# IO_FMU_REV_1A.net
KiCad netlist of a schematic drawn in Altium Designer
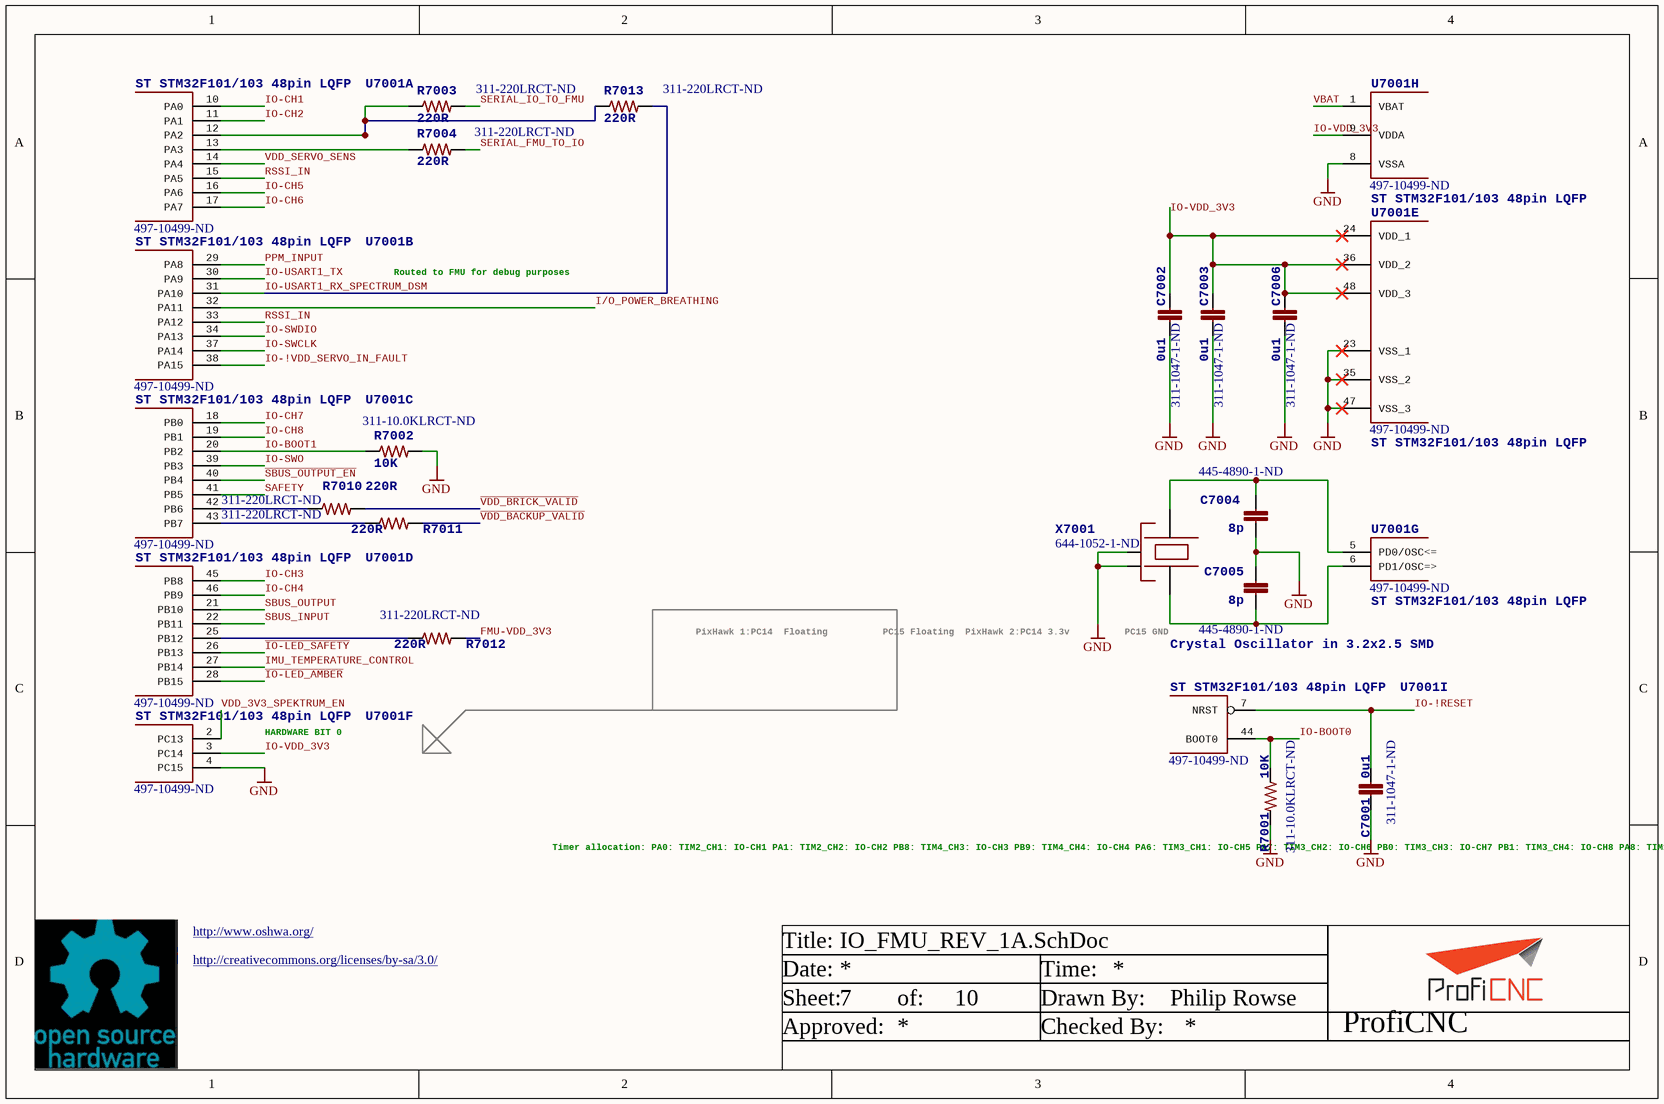
[diagram p0: IO_FMU_REV_1A.SchDoc]

(export (version "E")
  (design (tool "Eeschema 10.0.6"))
  (components
    (comp (ref "C7001")
      (value "0u1")
      (footprint "0402-CAP")
      (description "CAP CER 0.1UF 16V Y5V 0402")
      (fields
        (field (name "PARTNO") "CC0402ZRY5V7BB104")
        (field (name "SUPPLIER PART NUMBER 1") "311-1047-1-ND")
        (field (name "3DR_PARTNO") "ECM0700")
      )
      (libsource (lib "") (part "CAP0402_1"))
    )
    (comp (ref "C7002")
      (value "0u1")
      (footprint "0402-CAP")
      (description "CAP CER 0.1UF 16V Y5V 0402")
      (fields
        (field (name "PARTNO") "CC0402ZRY5V7BB104")
        (field (name "SUPPLIER PART NUMBER 1") "311-1047-1-ND")
        (field (name "3DR_PARTNO") "ECM0700")
      )
      (libsource (lib "pixhawk2") (part "CAP0402"))
    )
    (comp (ref "C7003")
      (value "0u1")
      (footprint "0402-CAP")
      (description "CAP CER 0.1UF 16V Y5V 0402")
      (fields
        (field (name "PARTNO") "CC0402ZRY5V7BB104")
        (field (name "SUPPLIER PART NUMBER 1") "311-1047-1-ND")
        (field (name "3DR_PARTNO") "ECM0700")
      )
      (libsource (lib "pixhawk2") (part "CAP0402"))
    )
    (comp (ref "C7004")
      (value "8p")
      (footprint "0402-CAP")
      (description "CAP CER 8PF 50V C0G 0402")
      (fields
        (field (name "PARTNO") "C1005C0G1H080C")
        (field (name "SUPPLIER PART NUMBER 1") "445-4890-1-ND")
        (field (name "3DR_PARTNO") "ECM0710")
      )
      (libsource (lib "pixhawk2") (part "CAP0402"))
    )
    (comp (ref "C7005")
      (value "8p")
      (footprint "0402-CAP")
      (description "CAP CER 8PF 50V C0G 0402")
      (fields
        (field (name "PARTNO") "C1005C0G1H080C")
        (field (name "SUPPLIER PART NUMBER 1") "445-4890-1-ND")
        (field (name "3DR_PARTNO") "ECM0710")
      )
      (libsource (lib "pixhawk2") (part "CAP0402"))
    )
    (comp (ref "C7006")
      (value "0u1")
      (footprint "0402-CAP")
      (description "CAP CER 0.1UF 16V Y5V 0402")
      (fields
        (field (name "PARTNO") "CC0402ZRY5V7BB104")
        (field (name "SUPPLIER PART NUMBER 1") "311-1047-1-ND")
        (field (name "3DR_PARTNO") "ECM0700")
      )
      (libsource (lib "pixhawk2") (part "CAP0402"))
    )
    (comp (ref "R7001")
      (value "10K")
      (footprint "0402-RES")
      (description "RES 10K OHM 1/16W 1% 0402 SMD")
      (fields
        (field (name "PARTNO") "RC0402FR-0710KL")
        (field (name "SUPPLIER PART NUMBER 1") "311-10.0KLRCT-ND")
        (field (name "3DR_PARTNO") "ECM0800")
      )
      (libsource (lib "pixhawk2") (part "RESISTOR0402-RES"))
    )
    (comp (ref "R7002")
      (value "10K")
      (footprint "0402-RES")
      (description "RES 10K OHM 1/16W 1% 0402 SMD")
      (fields
        (field (name "PARTNO") "RC0402FR-0710KL")
        (field (name "SUPPLIER PART NUMBER 1") "311-10.0KLRCT-ND")
        (field (name "3DR_PARTNO") "ECM0800")
      )
      (libsource (lib "pixhawk2") (part "RESISTOR0402-RES"))
    )
    (comp (ref "R7003")
      (value "220R")
      (footprint "0402-RES")
      (description "RES 220 OHM 1/16W 1% 0402 SMD")
      (fields
        (field (name "PARTNO") "RC0402FR-07220RL")
        (field (name "SUPPLIER PART NUMBER 1") "311-220LRCT-ND")
        (field (name "3DR_PARTNO") "ECM0821")
      )
      (libsource (lib "pixhawk2") (part "RESISTOR0402-RES"))
    )
    (comp (ref "R7004")
      (value "220R")
      (footprint "0402-RES")
      (description "RES 220 OHM 1/16W 1% 0402 SMD")
      (fields
        (field (name "PARTNO") "RC0402FR-07220RL")
        (field (name "SUPPLIER PART NUMBER 1") "311-220LRCT-ND")
        (field (name "3DR_PARTNO") "ECM0821")
      )
      (libsource (lib "pixhawk2") (part "RESISTOR0402-RES"))
    )
    (comp (ref "R7010")
      (value "220R")
      (footprint "0402-RES")
      (description "RES 220 OHM 1/16W 1% 0402 SMD")
      (fields
        (field (name "PARTNO") "RC0402FR-07220RL")
        (field (name "SUPPLIER PART NUMBER 1") "311-220LRCT-ND")
        (field (name "3DR_PARTNO") "ECM0821")
      )
      (libsource (lib "pixhawk2") (part "RESISTOR0402-RES"))
    )
    (comp (ref "R7011")
      (value "220R")
      (footprint "0402-RES")
      (description "RES 220 OHM 1/16W 1% 0402 SMD")
      (fields
        (field (name "PARTNO") "RC0402FR-07220RL")
        (field (name "SUPPLIER PART NUMBER 1") "311-220LRCT-ND")
        (field (name "3DR_PARTNO") "ECM0821")
      )
      (libsource (lib "pixhawk2") (part "RESISTOR0402-RES"))
    )
    (comp (ref "R7012")
      (value "220R")
      (footprint "0402-RES")
      (description "RES 220 OHM 1/16W 1% 0402 SMD")
      (fields
        (field (name "PARTNO") "RC0402FR-07220RL")
        (field (name "SUPPLIER PART NUMBER 1") "311-220LRCT-ND")
        (field (name "3DR_PARTNO") "ECM0821")
      )
      (libsource (lib "pixhawk2") (part "RESISTOR0402-RES"))
    )
    (comp (ref "R7013")
      (value "220R")
      (footprint "0402-RES")
      (description "RES 220 OHM 1/16W 1% 0402 SMD")
      (fields
        (field (name "PARTNO") "RC0402FR-07220RL")
        (field (name "SUPPLIER PART NUMBER 1") "311-220LRCT-ND")
        (field (name "3DR_PARTNO") "ECM0821")
      )
      (libsource (lib "pixhawk2") (part "RESISTOR0402-RES"))
    )
    (comp (ref "U7001")
      (value "ST STM32F101/103 48pin LQFP")
      (footprint "TQFP48")
      (description "MCU 32BIT ARM 64K FLASH 48LQFP")
      (fields (field (name "SUPPLIER PART NUMBER 1") "497-10499-ND") (field (name "3DR_PARTNO") "EMC0842"))
      (libsource (lib "pixhawk2") (part "STM32F10XCXT6"))
    )
    (comp (ref "X7001")
      (value "Crystal Oscillator in 3.2x2.5 SMD")
      (footprint "OSCILLATOR-3.2X2.5")
      (description "CRYSTAL 24MHZ 8PF SMD")
      (fields
        (field (name "SUPPLIER PART NUMBER 1") "644-1052-1-ND")
        (field (name "3DR_PARTNO") "ECM0708")
        (field (name "PARTNO") "NX3225SA-24.000MHZ-STD-CSR-1")
      )
      (libsource (lib "pixhawk2") (part "OSCILLATOR-3.2X2.5"))
    )
  )
  (nets
    (net (code "1") (name "/FMU-VDD_3V3") (class "Default")
      (node (ref "R7012") (pin "P$2") (pinfunction "2_P$2") (pintype "passive"))
    )
    (net (code "2") (name "/IMU_TEMPERATURE_CONTROL") (class "Default")
      (node (ref "U7001") (pin "27") (pinfunction "PB14_27") (pintype "passive"))
    )
    (net (code "3") (name "/IO-!RESET") (class "Default")
      (node (ref "C7001") (pin "P$2") (pinfunction "2_P$2") (pintype "passive"))
      (node (ref "U7001") (pin "7") (pinfunction "NRST_7") (pintype "passive"))
    )
    (net (code "4") (name "/IO-!VDD_SERVO_IN_FAULT") (class "Default")
      (node (ref "U7001") (pin "38") (pinfunction "PA15_38") (pintype "passive"))
    )
    (net (code "5") (name "/IO-BOOT0") (class "Default")
      (node (ref "R7001") (pin "P$1") (pinfunction "1_P$1") (pintype "passive"))
      (node (ref "U7001") (pin "44") (pinfunction "BOOT0_44") (pintype "passive"))
    )
    (net (code "6") (name "/IO-BOOT1") (class "Default")
      (node (ref "R7002") (pin "P$1") (pinfunction "1_P$1") (pintype "passive"))
      (node (ref "U7001") (pin "20") (pinfunction "PB2_20") (pintype "passive"))
    )
    (net (code "7") (name "/IO-CH1") (class "Default")
      (node (ref "U7001") (pin "10") (pinfunction "PA0_10") (pintype "passive"))
    )
    (net (code "8") (name "/IO-CH2") (class "Default")
      (node (ref "U7001") (pin "11") (pinfunction "PA1_11") (pintype "passive"))
    )
    (net (code "9") (name "/IO-CH3") (class "Default")
      (node (ref "U7001") (pin "45") (pinfunction "PB8_45") (pintype "passive"))
    )
    (net (code "10") (name "/IO-CH4") (class "Default")
      (node (ref "U7001") (pin "46") (pinfunction "PB9_46") (pintype "passive"))
    )
    (net (code "11") (name "/IO-CH5") (class "Default")
      (node (ref "U7001") (pin "16") (pinfunction "PA6_16") (pintype "passive"))
    )
    (net (code "12") (name "/IO-CH6") (class "Default")
      (node (ref "U7001") (pin "17") (pinfunction "PA7_17") (pintype "passive"))
    )
    (net (code "13") (name "/IO-CH7") (class "Default")
      (node (ref "U7001") (pin "18") (pinfunction "PB0_18") (pintype "passive"))
    )
    (net (code "14") (name "/IO-CH8") (class "Default")
      (node (ref "U7001") (pin "19") (pinfunction "PB1_19") (pintype "passive"))
    )
    (net (code "15") (name "/IO-SWCLK") (class "Default")
      (node (ref "U7001") (pin "37") (pinfunction "PA14_37") (pintype "passive"))
    )
    (net (code "16") (name "/IO-SWDIO") (class "Default")
      (node (ref "U7001") (pin "34") (pinfunction "PA13_34") (pintype "passive"))
    )
    (net (code "17") (name "/IO-SWO") (class "Default")
      (node (ref "U7001") (pin "39") (pinfunction "PB3_39") (pintype "passive"))
    )
    (net (code "18") (name "/IO-USART1_RX_SPECTRUM_DSM") (class "Default")
      (node (ref "R7013") (pin "P$2") (pinfunction "2_P$2") (pintype "passive"))
      (node (ref "U7001") (pin "31") (pinfunction "PA10_31") (pintype "passive"))
    )
    (net (code "19") (name "/IO-USART1_TX") (class "Default")
      (node (ref "U7001") (pin "30") (pinfunction "PA9_30") (pintype "passive"))
    )
    (net (code "20") (name "/IO-VDD_3V3") (class "Default")
      (node (ref "C7002") (pin "P$1") (pinfunction "1_P$1") (pintype "passive"))
      (node (ref "C7003") (pin "P$1") (pinfunction "1_P$1") (pintype "passive"))
      (node (ref "C7006") (pin "P$1") (pinfunction "1_P$1") (pintype "passive"))
      (node (ref "U7001") (pin "24") (pinfunction "VDD_1_24") (pintype "power_in"))
      (node (ref "U7001") (pin "3") (pinfunction "PC14_3") (pintype "passive"))
      (node (ref "U7001") (pin "36") (pinfunction "VDD_2_36") (pintype "power_in"))
      (node (ref "U7001") (pin "48") (pinfunction "VDD_3_48") (pintype "power_in"))
      (node (ref "U7001") (pin "9") (pinfunction "VDDA_9") (pintype "power_in"))
    )
    (net (code "21") (name "/I{slash}O_POWER_BREATHING") (class "Default")
      (node (ref "U7001") (pin "32") (pinfunction "PA11_32") (pintype "passive"))
    )
    (net (code "22") (name "/PPM_INPUT") (class "Default")
      (node (ref "U7001") (pin "29") (pinfunction "PA8_29") (pintype "passive"))
    )
    (net (code "23") (name "/RSSI_IN") (class "Default")
      (node (ref "U7001") (pin "15") (pinfunction "PA5_15") (pintype "passive"))
      (node (ref "U7001") (pin "33") (pinfunction "PA12_33") (pintype "passive"))
    )
    (net (code "24") (name "/SAFETY") (class "Default")
      (node (ref "U7001") (pin "41") (pinfunction "PB5_41") (pintype "passive"))
    )
    (net (code "25") (name "/SBUS_INPUT") (class "Default")
      (node (ref "U7001") (pin "22") (pinfunction "PB11_22") (pintype "passive"))
    )
    (net (code "26") (name "/SBUS_OUTPUT") (class "Default")
      (node (ref "U7001") (pin "21") (pinfunction "PB10_21") (pintype "passive"))
    )
    (net (code "27") (name "/SERIAL_FMU_TO_IO") (class "Default")
      (node (ref "R7004") (pin "P$2") (pinfunction "2_P$2") (pintype "passive"))
    )
    (net (code "28") (name "/SERIAL_IO_TO_FMU") (class "Default")
      (node (ref "R7003") (pin "P$2") (pinfunction "2_P$2") (pintype "passive"))
    )
    (net (code "29") (name "/VBAT") (class "Default")
      (node (ref "U7001") (pin "1") (pinfunction "VBAT_1") (pintype "power_in"))
    )
    (net (code "30") (name "/VDD_3V3_SPEKTRUM_EN") (class "Default")
      (node (ref "U7001") (pin "2") (pinfunction "PC13_2") (pintype "passive"))
    )
    (net (code "31") (name "/VDD_SERVO_SENS") (class "Default")
      (node (ref "U7001") (pin "14") (pinfunction "PA4_14") (pintype "passive"))
    )
    (net (code "32") (name "/~{IO-LED_AMBER}") (class "Default")
      (node (ref "U7001") (pin "28") (pinfunction "PB15_28") (pintype "passive"))
    )
    (net (code "33") (name "/~{IO-LED_SAFETY}") (class "Default")
      (node (ref "U7001") (pin "26") (pinfunction "PB13_26") (pintype "passive"))
    )
    (net (code "34") (name "/~{SBUS_OUTPUT_EN}") (class "Default")
      (node (ref "U7001") (pin "40") (pinfunction "PB4_40") (pintype "passive"))
    )
    (net (code "35") (name "/~{VDD_BACKUP_VALID}") (class "Default")
      (node (ref "R7011") (pin "P$2") (pinfunction "2_P$2") (pintype "passive"))
    )
    (net (code "36") (name "/~{VDD_BRICK_VALID}") (class "Default")
      (node (ref "R7010") (pin "P$2") (pinfunction "2_P$2") (pintype "passive"))
    )
    (net (code "37") (name "GND") (class "Default")
      (node (ref "C7001") (pin "P$1") (pinfunction "1_P$1") (pintype "passive"))
      (node (ref "C7002") (pin "P$2") (pinfunction "2_P$2") (pintype "passive"))
      (node (ref "C7003") (pin "P$2") (pinfunction "2_P$2") (pintype "passive"))
      (node (ref "C7004") (pin "P$2") (pinfunction "2_P$2") (pintype "passive"))
      (node (ref "C7005") (pin "P$1") (pinfunction "1_P$1") (pintype "passive"))
      (node (ref "C7006") (pin "P$2") (pinfunction "2_P$2") (pintype "passive"))
      (node (ref "R7001") (pin "P$2") (pinfunction "2_P$2") (pintype "passive"))
      (node (ref "R7002") (pin "P$2") (pinfunction "2_P$2") (pintype "passive"))
      (node (ref "U7001") (pin "23") (pinfunction "VSS_1_23") (pintype "power_in"))
      (node (ref "U7001") (pin "35") (pinfunction "VSS_2_35") (pintype "power_in"))
      (node (ref "U7001") (pin "4") (pinfunction "PC15_4") (pintype "passive"))
      (node (ref "U7001") (pin "47") (pinfunction "VSS_3_47") (pintype "power_in"))
      (node (ref "U7001") (pin "8") (pinfunction "VSSA_8") (pintype "power_in"))
      (node (ref "X7001") (pin "2") (pinfunction "NC_2_2") (pintype "open_emitter"))
      (node (ref "X7001") (pin "4") (pinfunction "NC_4_4") (pintype "open_emitter"))
    )
    (net (code "38") (name "Net-(C7004-1)") (class "Default")
      (node (ref "C7004") (pin "P$1") (pinfunction "1_P$1") (pintype "passive"))
      (node (ref "U7001") (pin "5") (pinfunction "PD0/OSC<=_5") (pintype "passive"))
      (node (ref "X7001") (pin "3") (pinfunction "3_3") (pintype "passive"))
    )
    (net (code "39") (name "Net-(C7005-2)") (class "Default")
      (node (ref "C7005") (pin "P$2") (pinfunction "2_P$2") (pintype "passive"))
      (node (ref "U7001") (pin "6") (pinfunction "PD1/OSC=>_6") (pintype "passive"))
      (node (ref "X7001") (pin "1") (pinfunction "1_1") (pintype "passive"))
    )
    (net (code "40") (name "Net-(R7003-1)") (class "Default")
      (node (ref "R7003") (pin "P$1") (pinfunction "1_P$1") (pintype "passive"))
      (node (ref "R7013") (pin "P$1") (pinfunction "1_P$1") (pintype "passive"))
      (node (ref "U7001") (pin "12") (pinfunction "PA2_12") (pintype "passive"))
    )
    (net (code "41") (name "Net-(R7004-1)") (class "Default")
      (node (ref "R7004") (pin "P$1") (pinfunction "1_P$1") (pintype "passive"))
      (node (ref "U7001") (pin "13") (pinfunction "PA3_13") (pintype "passive"))
    )
    (net (code "42") (name "Net-(R7010-1)") (class "Default")
      (node (ref "R7010") (pin "P$1") (pinfunction "1_P$1") (pintype "passive"))
      (node (ref "U7001") (pin "42") (pinfunction "PB6_42") (pintype "passive"))
    )
    (net (code "43") (name "Net-(R7011-1)") (class "Default")
      (node (ref "R7011") (pin "P$1") (pinfunction "1_P$1") (pintype "passive"))
      (node (ref "U7001") (pin "43") (pinfunction "PB7_43") (pintype "passive"))
    )
    (net (code "44") (name "Net-(R7012-1)") (class "Default")
      (node (ref "R7012") (pin "P$1") (pinfunction "1_P$1") (pintype "passive"))
      (node (ref "U7001") (pin "25") (pinfunction "PB12_25") (pintype "passive"))
    )
  )
)
